# Serial_I2C_Bridge_Prop.net
KiCad netlist of a schematic drawn in EAGLE
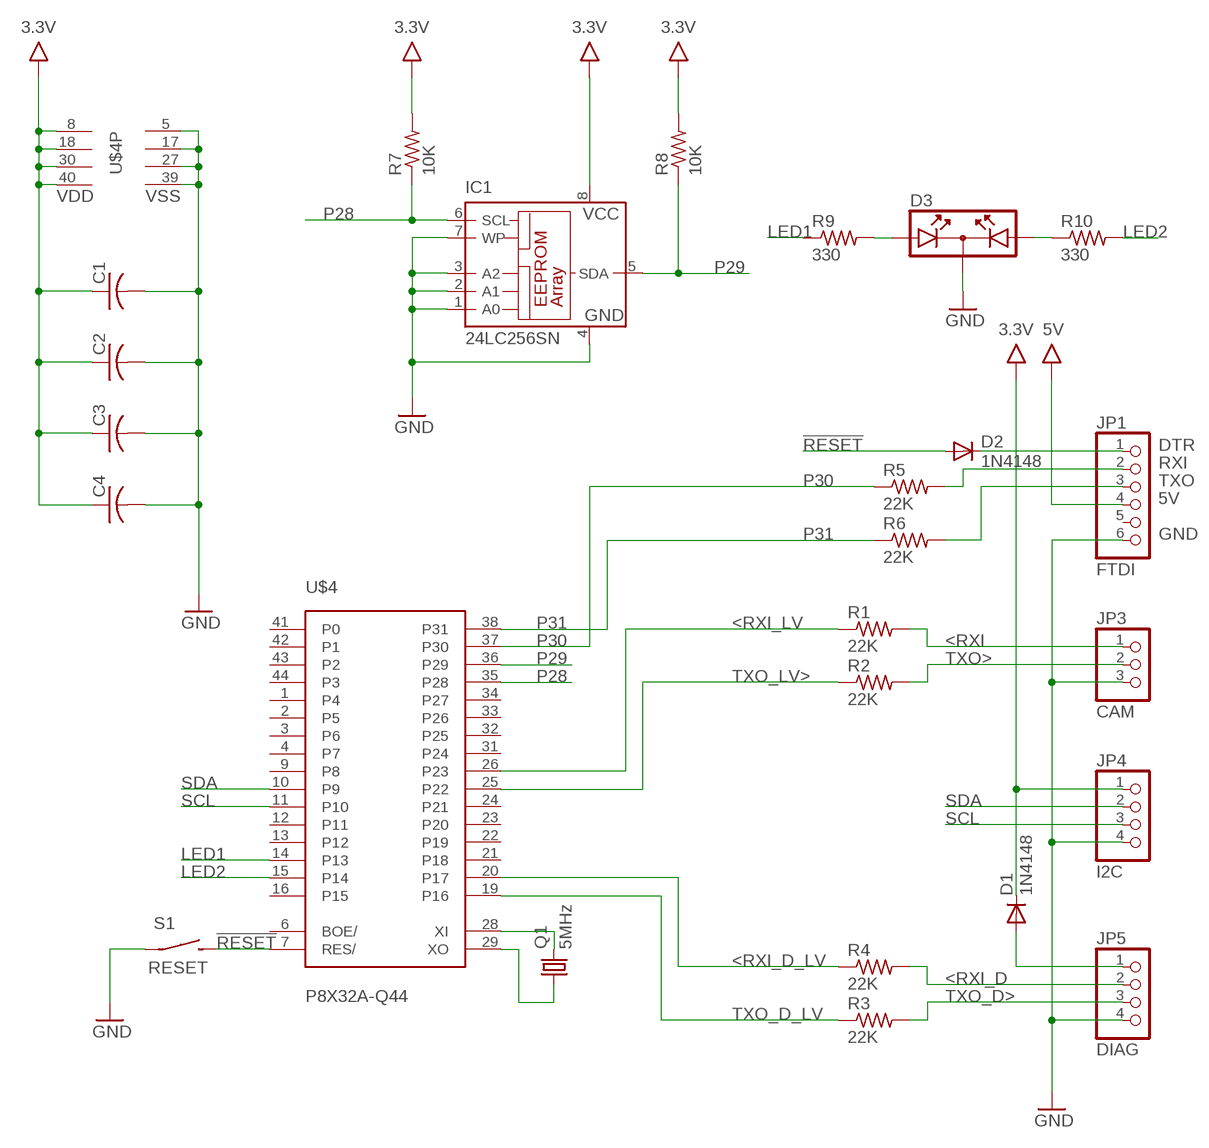
[diagram p0: schematic, sheet 1]

(export (version "E")
  (design (tool "Eeschema 10.0.6"))
  (components
    (comp (ref "C1")
      (value "C-USC0603")
      (footprint "eagle-import:C0603")
      (libsource (lib "eagle-import") (part "C-USC0603"))
    )
    (comp (ref "C2")
      (value "C-USC0603")
      (footprint "eagle-import:C0603")
      (libsource (lib "eagle-import") (part "C-USC0603"))
    )
    (comp (ref "C3")
      (value "C-USC0603")
      (footprint "eagle-import:C0603")
      (libsource (lib "eagle-import") (part "C-USC0603"))
    )
    (comp (ref "C4")
      (value "C-USC0603")
      (footprint "eagle-import:C0603")
      (libsource (lib "eagle-import") (part "C-USC0603"))
    )
    (comp (ref "D1")
      (value "1N4148")
      (footprint "eagle-import:DO35-7")
      (libsource (lib "eagle-import") (part "1N4148DO35-7"))
    )
    (comp (ref "D2")
      (value "1N4148")
      (footprint "eagle-import:DO35-7")
      (libsource (lib "eagle-import") (part "1N4148DO35-7"))
    )
    (comp (ref "D3")
      (value "DUOLED")
      (footprint "eagle-import:DUOLED")
      (libsource (lib "eagle-import") (part "DUOLED"))
    )
    (comp (ref "IC1")
      (value "24LC256SN")
      (footprint "eagle-import:SO-08")
      (fields (field (name "MF") "MICROCHIP") (field (name "MPN") "24LC256-I/SN"))
      (libsource (lib "eagle-import") (part "24SNLC256"))
    )
    (comp (ref "JP1")
      (value "FTDI")
      (footprint "eagle-import:1X06")
      (libsource (lib "eagle-import") (part "PINHD-1X06_2.54"))
    )
    (comp (ref "JP3")
      (value "CAM")
      (footprint "eagle-import:1X03")
      (libsource (lib "eagle-import") (part "PINHD-1X03_2.54"))
    )
    (comp (ref "JP4")
      (value "I2C")
      (footprint "eagle-import:1X04")
      (libsource (lib "eagle-import") (part "PINHD-1X04_2.54"))
    )
    (comp (ref "JP5")
      (value "DIAG")
      (footprint "eagle-import:1X04")
      (libsource (lib "eagle-import") (part "PINHD-1X04_2.54"))
    )
    (comp (ref "Q1")
      (value "5MHz")
      (footprint "eagle-import:HC49_S")
      (libsource (lib "eagle-import") (part "CRYSTALHC49S"))
    )
    (comp (ref "R1")
      (value "22K")
      (footprint "eagle-import:0204_5")
      (libsource (lib "eagle-import") (part "R-US_0204/5"))
    )
    (comp (ref "R2")
      (value "22K")
      (footprint "eagle-import:0204_5")
      (libsource (lib "eagle-import") (part "R-US_0204/5"))
    )
    (comp (ref "R3")
      (value "22K")
      (footprint "eagle-import:0204_5")
      (libsource (lib "eagle-import") (part "R-US_0204/5"))
    )
    (comp (ref "R4")
      (value "22K")
      (footprint "eagle-import:0204_5")
      (libsource (lib "eagle-import") (part "R-US_0204/5"))
    )
    (comp (ref "R5")
      (value "22K")
      (footprint "eagle-import:0204_5")
      (libsource (lib "eagle-import") (part "R-US_0204/5"))
    )
    (comp (ref "R6")
      (value "22K")
      (footprint "eagle-import:0204_5")
      (libsource (lib "eagle-import") (part "R-US_0204/5"))
    )
    (comp (ref "R7")
      (value "10K")
      (footprint "eagle-import:0204_5")
      (libsource (lib "eagle-import") (part "R-US_0204/5"))
    )
    (comp (ref "R8")
      (value "10K")
      (footprint "eagle-import:0204_5")
      (libsource (lib "eagle-import") (part "R-US_0204/5"))
    )
    (comp (ref "R9")
      (value "330")
      (footprint "eagle-import:0204_5")
      (libsource (lib "eagle-import") (part "R-US_0204/5"))
    )
    (comp (ref "R10")
      (value "330")
      (footprint "eagle-import:0204_5")
      (libsource (lib "eagle-import") (part "R-US_0204/5"))
    )
    (comp (ref "S1")
      (value "RESET")
      (footprint "eagle-import:6MMTACTILE")
      (libsource (lib "eagle-import") (part "SPSTTACTILE2"))
    )
    (comp (ref "U$4")
      (value "P8X32A-Q44")
      (footprint "eagle-import:P8X32A-Q44")
      (libsource (lib "eagle-import") (part "P8X32A-Q44"))
    )
  )
  (nets
    (net (code "1") (name "/<RXI") (class "Default")
      (node (ref "JP3") (pin "1") (pinfunction "1_1") (pintype "passive"))
      (node (ref "R1") (pin "2") (pinfunction "2_2") (pintype "passive"))
    )
    (net (code "2") (name "/<RXI_D") (class "Default")
      (node (ref "JP5") (pin "2") (pinfunction "2_2") (pintype "passive"))
      (node (ref "R4") (pin "2") (pinfunction "2_2") (pintype "passive"))
    )
    (net (code "3") (name "/<RXI_D_LV") (class "Default")
      (node (ref "R4") (pin "1") (pinfunction "1_1") (pintype "passive"))
      (node (ref "U$4") (pin "20") (pinfunction "P17_20") (pintype "bidirectional"))
    )
    (net (code "4") (name "/<RXI_LV") (class "Default")
      (node (ref "R1") (pin "1") (pinfunction "1_1") (pintype "passive"))
      (node (ref "U$4") (pin "26") (pinfunction "P23_26") (pintype "bidirectional"))
    )
    (net (code "5") (name "/LED1") (class "Default")
      (node (ref "R9") (pin "1") (pinfunction "1_1") (pintype "passive"))
      (node (ref "U$4") (pin "14") (pinfunction "P13_14") (pintype "bidirectional"))
    )
    (net (code "6") (name "/LED2") (class "Default")
      (node (ref "R10") (pin "2") (pinfunction "2_2") (pintype "passive"))
      (node (ref "U$4") (pin "15") (pinfunction "P14_15") (pintype "bidirectional"))
    )
    (net (code "7") (name "/P28") (class "Default")
      (node (ref "IC1") (pin "6") (pinfunction "SCL_6") (pintype "input"))
      (node (ref "R7") (pin "1") (pinfunction "1_1") (pintype "passive"))
      (node (ref "U$4") (pin "35") (pinfunction "P28_35") (pintype "bidirectional"))
    )
    (net (code "8") (name "/P29") (class "Default")
      (node (ref "IC1") (pin "5") (pinfunction "SDA_5") (pintype "bidirectional"))
      (node (ref "R8") (pin "1") (pinfunction "1_1") (pintype "passive"))
      (node (ref "U$4") (pin "36") (pinfunction "P29_36") (pintype "bidirectional"))
    )
    (net (code "9") (name "/P30") (class "Default")
      (node (ref "R5") (pin "1") (pinfunction "1_1") (pintype "passive"))
      (node (ref "U$4") (pin "37") (pinfunction "P30_37") (pintype "bidirectional"))
    )
    (net (code "10") (name "/P31") (class "Default")
      (node (ref "R6") (pin "1") (pinfunction "1_1") (pintype "passive"))
      (node (ref "U$4") (pin "38") (pinfunction "P31_38") (pintype "bidirectional"))
    )
    (net (code "11") (name "/SCL") (class "Default")
      (node (ref "JP4") (pin "3") (pinfunction "3_3") (pintype "passive"))
      (node (ref "U$4") (pin "11") (pinfunction "P10_11") (pintype "bidirectional"))
    )
    (net (code "12") (name "/SDA") (class "Default")
      (node (ref "JP4") (pin "2") (pinfunction "2_2") (pintype "passive"))
      (node (ref "U$4") (pin "10") (pinfunction "P9_10") (pintype "bidirectional"))
    )
    (net (code "13") (name "/TXO>") (class "Default")
      (node (ref "JP3") (pin "2") (pinfunction "2_2") (pintype "passive"))
      (node (ref "R2") (pin "2") (pinfunction "2_2") (pintype "passive"))
    )
    (net (code "14") (name "/TXO_D>") (class "Default")
      (node (ref "JP5") (pin "3") (pinfunction "3_3") (pintype "passive"))
      (node (ref "R3") (pin "2") (pinfunction "2_2") (pintype "passive"))
    )
    (net (code "15") (name "/TXO_D_LV") (class "Default")
      (node (ref "R3") (pin "1") (pinfunction "1_1") (pintype "passive"))
      (node (ref "U$4") (pin "19") (pinfunction "P16_19") (pintype "bidirectional"))
    )
    (net (code "16") (name "/TXO_LV>") (class "Default")
      (node (ref "R2") (pin "1") (pinfunction "1_1") (pintype "passive"))
      (node (ref "U$4") (pin "25") (pinfunction "P22_25") (pintype "bidirectional"))
    )
    (net (code "17") (name "/~{RESET}") (class "Default")
      (node (ref "D2") (pin "A") (pinfunction "A_A") (pintype "passive"))
      (node (ref "S1") (pin "P$2") (pinfunction "S_P$2") (pintype "passive"))
      (node (ref "U$4") (pin "7") (pinfunction "RES/_7") (pintype "bidirectional"))
    )
    (net (code "18") (name "3.3V") (class "Default")
      (node (ref "C1") (pin "1") (pinfunction "1_1") (pintype "passive"))
      (node (ref "C2") (pin "1") (pinfunction "1_1") (pintype "passive"))
      (node (ref "C3") (pin "1") (pinfunction "1_1") (pintype "passive"))
      (node (ref "C4") (pin "1") (pinfunction "1_1") (pintype "passive"))
      (node (ref "D1") (pin "C") (pinfunction "C_C") (pintype "passive"))
      (node (ref "IC1") (pin "8") (pinfunction "VCC_8") (pintype "power_in"))
      (node (ref "JP4") (pin "1") (pinfunction "1_1") (pintype "passive"))
      (node (ref "R7") (pin "2") (pinfunction "2_2") (pintype "passive"))
      (node (ref "R8") (pin "2") (pinfunction "2_2") (pintype "passive"))
      (node (ref "U$4") (pin "18") (pinfunction "VDD_18") (pintype "power_in"))
      (node (ref "U$4") (pin "30") (pinfunction "VDD_30") (pintype "power_in"))
      (node (ref "U$4") (pin "40") (pinfunction "VDD_40") (pintype "power_in"))
      (node (ref "U$4") (pin "8") (pinfunction "VDD_8") (pintype "power_in"))
    )
    (net (code "19") (name "5V") (class "Default")
      (node (ref "JP1") (pin "4") (pinfunction "4_4") (pintype "passive"))
    )
    (net (code "20") (name "GND") (class "Default")
      (node (ref "C1") (pin "2") (pinfunction "2_2") (pintype "passive"))
      (node (ref "C2") (pin "2") (pinfunction "2_2") (pintype "passive"))
      (node (ref "C3") (pin "2") (pinfunction "2_2") (pintype "passive"))
      (node (ref "C4") (pin "2") (pinfunction "2_2") (pintype "passive"))
      (node (ref "D3") (pin "K") (pinfunction "K_K") (pintype "passive"))
      (node (ref "IC1") (pin "1") (pinfunction "A0_1") (pintype "input"))
      (node (ref "IC1") (pin "2") (pinfunction "A1_2") (pintype "input"))
      (node (ref "IC1") (pin "3") (pinfunction "A2_3") (pintype "input"))
      (node (ref "IC1") (pin "4") (pinfunction "GND_4") (pintype "power_in"))
      (node (ref "IC1") (pin "7") (pinfunction "WP_7") (pintype "input"))
      (node (ref "JP1") (pin "6") (pinfunction "6_6") (pintype "passive"))
      (node (ref "JP3") (pin "3") (pinfunction "3_3") (pintype "passive"))
      (node (ref "JP4") (pin "4") (pinfunction "4_4") (pintype "passive"))
      (node (ref "JP5") (pin "4") (pinfunction "4_4") (pintype "passive"))
      (node (ref "S1") (pin "P$1") (pinfunction "P_P$1") (pintype "passive"))
      (node (ref "U$4") (pin "17") (pinfunction "VSS_17") (pintype "power_in"))
      (node (ref "U$4") (pin "27") (pinfunction "VSS_27") (pintype "power_in"))
      (node (ref "U$4") (pin "39") (pinfunction "VSS_39") (pintype "power_in"))
      (node (ref "U$4") (pin "5") (pinfunction "VSS_5") (pintype "power_in"))
    )
    (net (code "21") (name "Net-(D1-PadA)") (class "Default")
      (node (ref "D1") (pin "A") (pinfunction "A_A") (pintype "passive"))
      (node (ref "JP5") (pin "1") (pinfunction "1_1") (pintype "passive"))
    )
    (net (code "22") (name "Net-(D2-PadC)") (class "Default")
      (node (ref "D2") (pin "C") (pinfunction "C_C") (pintype "passive"))
      (node (ref "JP1") (pin "1") (pinfunction "1_1") (pintype "passive"))
    )
    (net (code "23") (name "Net-(D3-PadA1)") (class "Default")
      (node (ref "D3") (pin "A1") (pinfunction "A1_A1") (pintype "passive"))
      (node (ref "R9") (pin "2") (pinfunction "2_2") (pintype "passive"))
    )
    (net (code "24") (name "Net-(D3-PadA2)") (class "Default")
      (node (ref "D3") (pin "A2") (pinfunction "A2_A2") (pintype "passive"))
      (node (ref "R10") (pin "1") (pinfunction "1_1") (pintype "passive"))
    )
    (net (code "25") (name "Net-(JP1-Pad2)") (class "Default")
      (node (ref "JP1") (pin "2") (pinfunction "2_2") (pintype "passive"))
      (node (ref "R5") (pin "2") (pinfunction "2_2") (pintype "passive"))
    )
    (net (code "26") (name "Net-(JP1-Pad3)") (class "Default")
      (node (ref "JP1") (pin "3") (pinfunction "3_3") (pintype "passive"))
      (node (ref "R6") (pin "2") (pinfunction "2_2") (pintype "passive"))
    )
    (net (code "27") (name "Net-(U$4B-XI)") (class "Default")
      (node (ref "Q1") (pin "2") (pinfunction "2_2") (pintype "passive"))
      (node (ref "U$4") (pin "28") (pinfunction "XI_28") (pintype "input"))
    )
    (net (code "28") (name "Net-(U$4B-XO)") (class "Default")
      (node (ref "Q1") (pin "1") (pinfunction "1_1") (pintype "passive"))
      (node (ref "U$4") (pin "29") (pinfunction "XO_29") (pintype "output"))
    )
    (net (code "29") (name "unconnected-(JP1-Pad5)") (class "Default")
      (node (ref "JP1") (pin "5") (pinfunction "5_5") (pintype "passive"))
    )
    (net (code "30") (name "unconnected-(U$4B-BOE{slash}-Pad6)") (class "Default")
      (node (ref "U$4") (pin "6") (pinfunction "BOE/_6") (pintype "input"))
    )
    (net (code "31") (name "unconnected-(U$4B-P0-Pad41)") (class "Default")
      (node (ref "U$4") (pin "41") (pinfunction "P0_41") (pintype "bidirectional"))
    )
    (net (code "32") (name "unconnected-(U$4B-P1-Pad42)") (class "Default")
      (node (ref "U$4") (pin "42") (pinfunction "P1_42") (pintype "bidirectional"))
    )
    (net (code "33") (name "unconnected-(U$4B-P2-Pad43)") (class "Default")
      (node (ref "U$4") (pin "43") (pinfunction "P2_43") (pintype "bidirectional"))
    )
    (net (code "34") (name "unconnected-(U$4B-P3-Pad44)") (class "Default")
      (node (ref "U$4") (pin "44") (pinfunction "P3_44") (pintype "bidirectional"))
    )
    (net (code "35") (name "unconnected-(U$4B-P4-Pad1)") (class "Default")
      (node (ref "U$4") (pin "1") (pinfunction "P4_1") (pintype "bidirectional"))
    )
    (net (code "36") (name "unconnected-(U$4B-P5-Pad2)") (class "Default")
      (node (ref "U$4") (pin "2") (pinfunction "P5_2") (pintype "bidirectional"))
    )
    (net (code "37") (name "unconnected-(U$4B-P6-Pad3)") (class "Default")
      (node (ref "U$4") (pin "3") (pinfunction "P6_3") (pintype "bidirectional"))
    )
    (net (code "38") (name "unconnected-(U$4B-P7-Pad4)") (class "Default")
      (node (ref "U$4") (pin "4") (pinfunction "P7_4") (pintype "bidirectional"))
    )
    (net (code "39") (name "unconnected-(U$4B-P8-Pad9)") (class "Default")
      (node (ref "U$4") (pin "9") (pinfunction "P8_9") (pintype "bidirectional"))
    )
    (net (code "40") (name "unconnected-(U$4B-P11-Pad12)") (class "Default")
      (node (ref "U$4") (pin "12") (pinfunction "P11_12") (pintype "bidirectional"))
    )
    (net (code "41") (name "unconnected-(U$4B-P12-Pad13)") (class "Default")
      (node (ref "U$4") (pin "13") (pinfunction "P12_13") (pintype "bidirectional"))
    )
    (net (code "42") (name "unconnected-(U$4B-P15-Pad16)") (class "Default")
      (node (ref "U$4") (pin "16") (pinfunction "P15_16") (pintype "bidirectional"))
    )
    (net (code "43") (name "unconnected-(U$4B-P18-Pad21)") (class "Default")
      (node (ref "U$4") (pin "21") (pinfunction "P18_21") (pintype "bidirectional"))
    )
    (net (code "44") (name "unconnected-(U$4B-P19-Pad22)") (class "Default")
      (node (ref "U$4") (pin "22") (pinfunction "P19_22") (pintype "bidirectional"))
    )
    (net (code "45") (name "unconnected-(U$4B-P20-Pad23)") (class "Default")
      (node (ref "U$4") (pin "23") (pinfunction "P20_23") (pintype "bidirectional"))
    )
    (net (code "46") (name "unconnected-(U$4B-P21-Pad24)") (class "Default")
      (node (ref "U$4") (pin "24") (pinfunction "P21_24") (pintype "bidirectional"))
    )
    (net (code "47") (name "unconnected-(U$4B-P24-Pad31)") (class "Default")
      (node (ref "U$4") (pin "31") (pinfunction "P24_31") (pintype "bidirectional"))
    )
    (net (code "48") (name "unconnected-(U$4B-P25-Pad32)") (class "Default")
      (node (ref "U$4") (pin "32") (pinfunction "P25_32") (pintype "bidirectional"))
    )
    (net (code "49") (name "unconnected-(U$4B-P26-Pad33)") (class "Default")
      (node (ref "U$4") (pin "33") (pinfunction "P26_33") (pintype "bidirectional"))
    )
    (net (code "50") (name "unconnected-(U$4B-P27-Pad34)") (class "Default")
      (node (ref "U$4") (pin "34") (pinfunction "P27_34") (pintype "bidirectional"))
    )
  )
)
